# MM4_r0.net
KiCad netlist of a schematic drawn in EAGLE
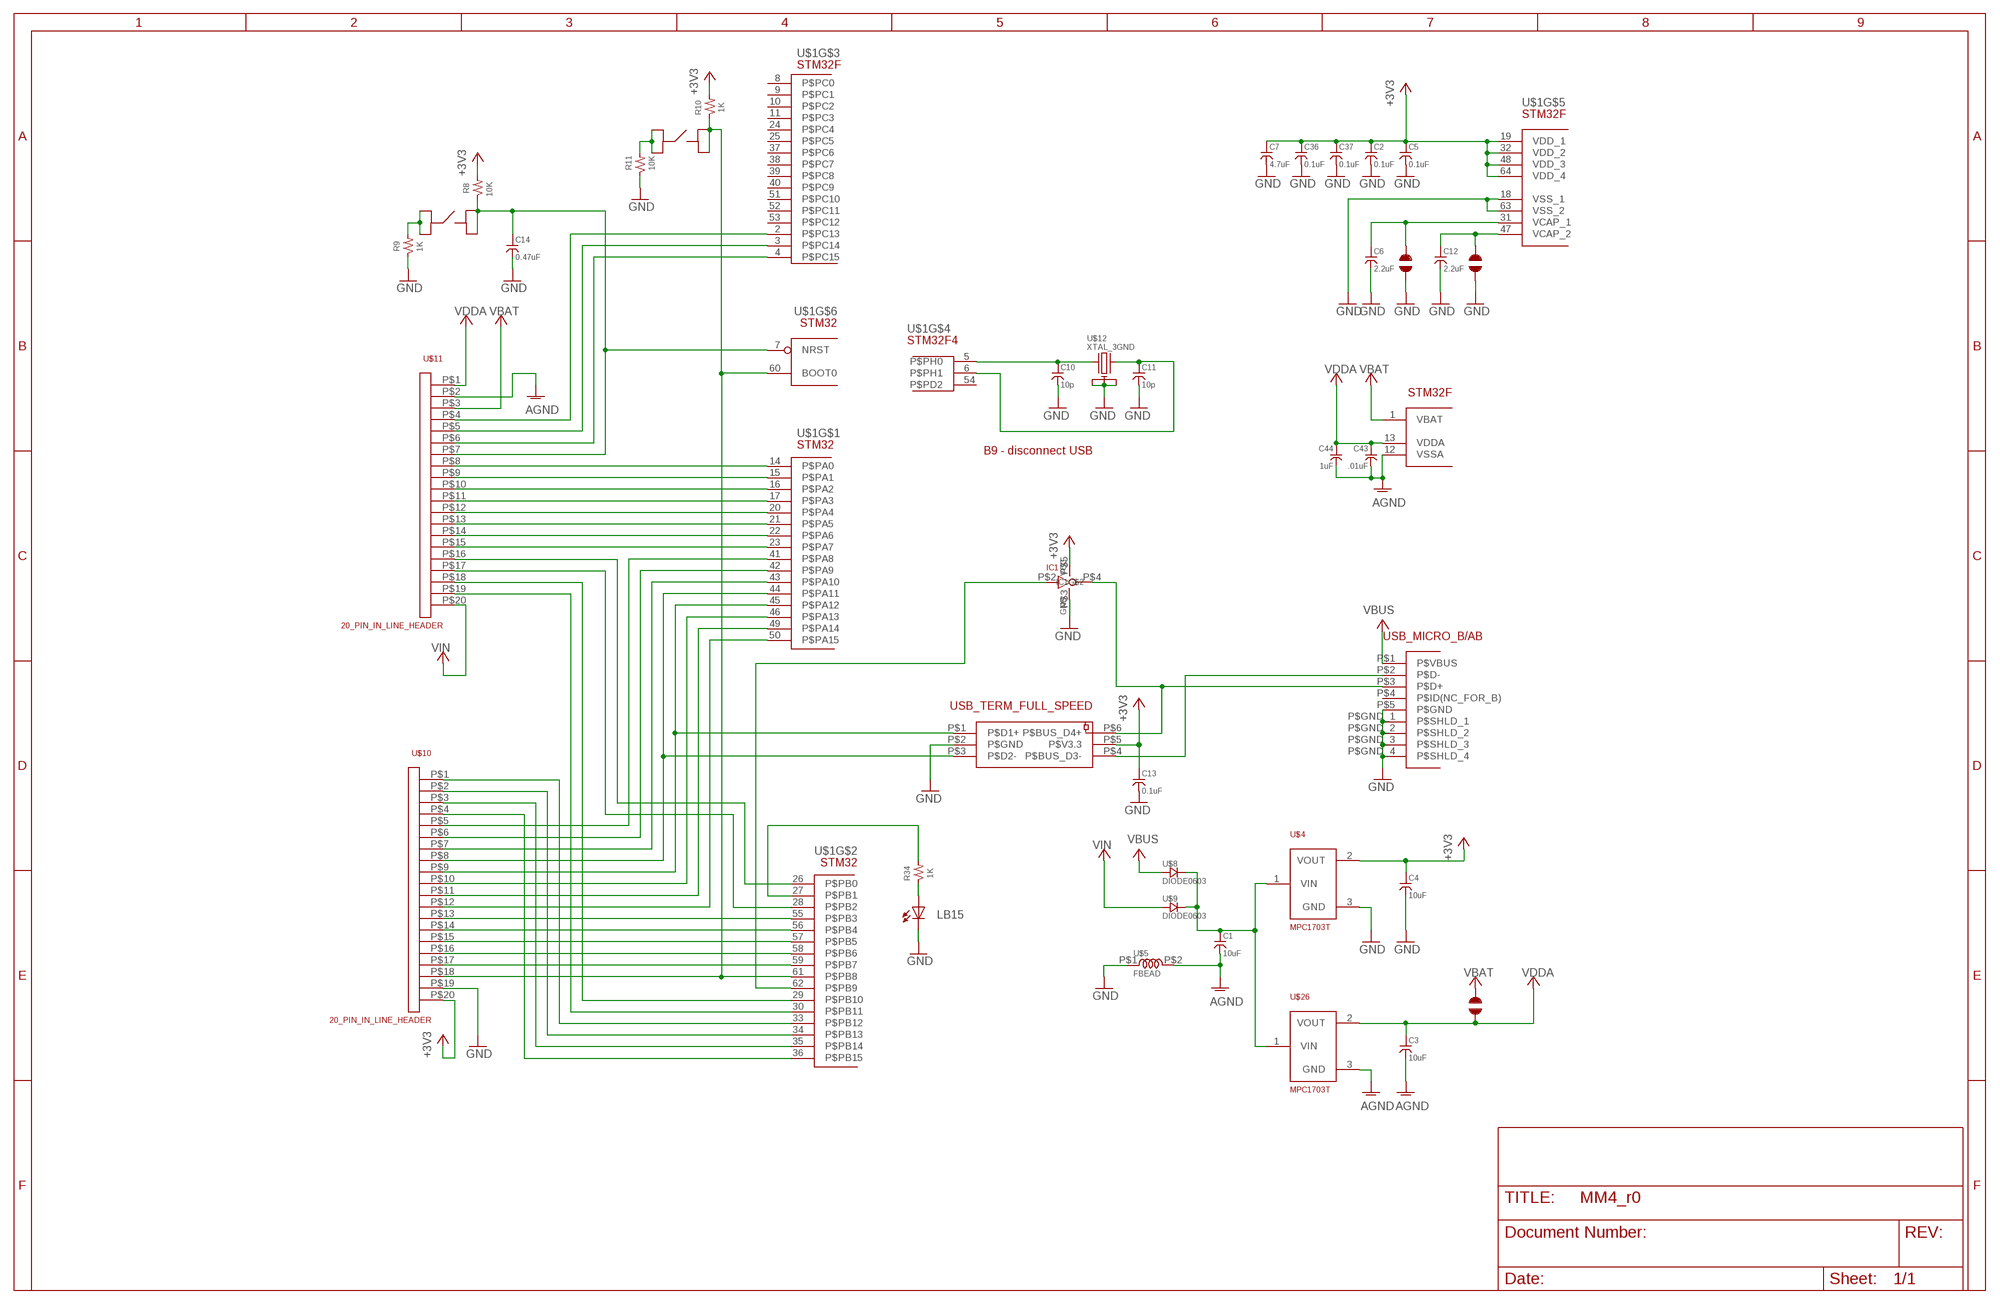
[diagram p0: schematic, sheet 1]

(export (version "E")
  (design (tool "Eeschema 10.0.6"))
  (components
    (comp (ref "C1")
      (value "10uF")
      (footprint "eagle-import:0603")
      (libsource (lib "eagle-import") (part "CAP0603"))
    )
    (comp (ref "C2")
      (value "0.1uF")
      (footprint "eagle-import:0603")
      (libsource (lib "eagle-import") (part "CAP0603"))
    )
    (comp (ref "C3")
      (value "10uF")
      (footprint "eagle-import:0603")
      (libsource (lib "eagle-import") (part "CAP0603"))
    )
    (comp (ref "C4")
      (value "10uF")
      (footprint "eagle-import:0603")
      (libsource (lib "eagle-import") (part "CAP0603"))
    )
    (comp (ref "C5")
      (value "0.1uF")
      (footprint "eagle-import:0603")
      (libsource (lib "eagle-import") (part "CAP0603"))
    )
    (comp (ref "C6")
      (value "2.2uF")
      (footprint "eagle-import:0603")
      (libsource (lib "eagle-import") (part "CAP0603"))
    )
    (comp (ref "C7")
      (value "4.7uF")
      (footprint "eagle-import:0603")
      (libsource (lib "eagle-import") (part "CAP0603"))
    )
    (comp (ref "C10")
      (value "10p")
      (footprint "eagle-import:0603")
      (libsource (lib "eagle-import") (part "CAP0603"))
    )
    (comp (ref "C11")
      (value "10p")
      (footprint "eagle-import:0603")
      (libsource (lib "eagle-import") (part "CAP0603"))
    )
    (comp (ref "C12")
      (value "2.2uF")
      (footprint "eagle-import:0603")
      (libsource (lib "eagle-import") (part "CAP0603"))
    )
    (comp (ref "C13")
      (value "0.1uF")
      (footprint "eagle-import:0603")
      (libsource (lib "eagle-import") (part "CAP0603"))
    )
    (comp (ref "C14")
      (value "0.47uF")
      (footprint "eagle-import:0603")
      (libsource (lib "eagle-import") (part "CAP0603"))
    )
    (comp (ref "C36")
      (value "0.1uF")
      (footprint "eagle-import:0603")
      (libsource (lib "eagle-import") (part "CAP0603"))
    )
    (comp (ref "C37")
      (value "0.1uF")
      (footprint "eagle-import:0603")
      (libsource (lib "eagle-import") (part "CAP0603"))
    )
    (comp (ref "C43")
      (value ".01uF")
      (footprint "eagle-import:0603")
      (libsource (lib "eagle-import") (part "CAP0603"))
    )
    (comp (ref "C44")
      (value "1uF")
      (footprint "eagle-import:0603")
      (libsource (lib "eagle-import") (part "CAP0603"))
    )
    (comp (ref "IC1")
      (value "7SZ05")
      (footprint "eagle-import:SC-70-5")
      (libsource (lib "eagle-import") (part "LOG_7SZ05"))
    )
    (comp (ref "LB15")
      (value "LED_CMD280603+")
      (footprint "eagle-import:0603+")
      (libsource (lib "eagle-import") (part "LED_CMD280603+"))
    )
    (comp (ref "R8")
      (value "10K")
      (footprint "eagle-import:0603")
      (libsource (lib "eagle-import") (part "RESISTOR0603"))
    )
    (comp (ref "R9")
      (value "1K")
      (footprint "eagle-import:0603")
      (libsource (lib "eagle-import") (part "RESISTOR0603"))
    )
    (comp (ref "R10")
      (value "1K")
      (footprint "eagle-import:0603")
      (libsource (lib "eagle-import") (part "RESISTOR0603"))
    )
    (comp (ref "R11")
      (value "10K")
      (footprint "eagle-import:0603")
      (libsource (lib "eagle-import") (part "RESISTOR0603"))
    )
    (comp (ref "R34")
      (value "1K")
      (footprint "eagle-import:0603")
      (libsource (lib "eagle-import") (part "RESISTOR0603"))
    )
    (comp (ref "U$1")
      (value "STM32F40XRG")
      (footprint "eagle-import:TQFP64")
      (libsource (lib "eagle-import") (part "STM32F40XRG"))
    )
    (comp (ref "U$2")
      (value "JUMPER_SOLDER")
      (footprint "eagle-import:JUMPER")
      (libsource (lib "eagle-import") (part "JUMPER_SOLDER"))
    )
    (comp (ref "U$3")
      (value "JUMPER_SOLDER")
      (footprint "eagle-import:JUMPER")
      (libsource (lib "eagle-import") (part "JUMPER_SOLDER"))
    )
    (comp (ref "U$4")
      (value "MPC1703T")
      (footprint "eagle-import:SOT23-3")
      (libsource (lib "eagle-import") (part "MPC1703T"))
    )
    (comp (ref "U$5")
      (value "FBEAD")
      (footprint "eagle-import:BEAD_0603")
      (libsource (lib "eagle-import") (part "FBEAD"))
    )
    (comp (ref "U$8")
      (value "DIODE0603")
      (footprint "eagle-import:0603_DIODE")
      (libsource (lib "eagle-import") (part "DIODE0603"))
    )
    (comp (ref "U$9")
      (value "DIODE0603")
      (footprint "eagle-import:0603_DIODE")
      (libsource (lib "eagle-import") (part "DIODE0603"))
    )
    (comp (ref "U$10")
      (value "20_PIN_IN_LINE_HEADER")
      (footprint "eagle-import:20_PIN_IN_LINE")
      (libsource (lib "eagle-import") (part "20_PIN_IN_LINE_HEADER"))
    )
    (comp (ref "U$11")
      (value "20_PIN_IN_LINE_HEADER")
      (footprint "eagle-import:20_PIN_IN_LINE")
      (libsource (lib "eagle-import") (part "20_PIN_IN_LINE_HEADER"))
    )
    (comp (ref "U$12")
      (value "XTAL_3GND")
      (footprint "eagle-import:XTAL=TXC7M-3")
      (libsource (lib "eagle-import") (part "XTAL_3GND"))
    )
    (comp (ref "U$13")
      (value "JUMPER_SOLDER")
      (footprint "eagle-import:JUMPER")
      (libsource (lib "eagle-import") (part "JUMPER_SOLDER"))
    )
    (comp (ref "U$14")
      (value "MICRO_USB_B")
      (footprint "eagle-import:USB-ZX-62-B-5PA")
      (libsource (lib "eagle-import") (part "MICRO_USB_BMICRO"))
    )
    (comp (ref "U$23")
      (value "USB_TERM_FS")
      (footprint "eagle-import:SOT-666IP")
      (libsource (lib "eagle-import") (part "USB_TERM_FS"))
    )
    (comp (ref "U$24")
      (value "SW_SMD_TACTILE")
      (footprint "eagle-import:SW_SMD_TACTILE")
      (libsource (lib "eagle-import") (part "SW_SMD_TACTILE"))
    )
    (comp (ref "U$25")
      (value "SW_SMD_TACTILE")
      (footprint "eagle-import:SW_SMD_TACTILE")
      (libsource (lib "eagle-import") (part "SW_SMD_TACTILE"))
    )
    (comp (ref "U$26")
      (value "MPC1703T")
      (footprint "eagle-import:SOT23-3")
      (libsource (lib "eagle-import") (part "MPC1703T"))
    )
  )
  (nets
    (net (code "1") (name "+3V3") (class "Default")
      (node (ref "C13") (pin "P$1") (pinfunction "P$1_P$1") (pintype "passive"))
      (node (ref "C2") (pin "P$1") (pinfunction "P$1_P$1") (pintype "passive"))
      (node (ref "C36") (pin "P$1") (pinfunction "P$1_P$1") (pintype "passive"))
      (node (ref "C37") (pin "P$1") (pinfunction "P$1_P$1") (pintype "passive"))
      (node (ref "C4") (pin "P$1") (pinfunction "P$1_P$1") (pintype "passive"))
      (node (ref "C5") (pin "P$1") (pinfunction "P$1_P$1") (pintype "passive"))
      (node (ref "C7") (pin "P$1") (pinfunction "P$1_P$1") (pintype "passive"))
      (node (ref "IC1") (pin "P$5") (pinfunction "VCC_P$5") (pintype "power_in"))
      (node (ref "R10") (pin "P$1") (pinfunction "P$2_P$1") (pintype "passive"))
      (node (ref "R8") (pin "P$1") (pinfunction "P$2_P$1") (pintype "passive"))
      (node (ref "U$1") (pin "19") (pinfunction "VDD_1_19") (pintype "power_in"))
      (node (ref "U$1") (pin "32") (pinfunction "VDD_2_32") (pintype "power_in"))
      (node (ref "U$1") (pin "48") (pinfunction "VDD_3_48") (pintype "power_in"))
      (node (ref "U$1") (pin "64") (pinfunction "VDD_4_64") (pintype "power_in"))
      (node (ref "U$10") (pin "P$20") (pinfunction "P$20_P$20") (pintype "bidirectional"))
      (node (ref "U$23") (pin "P$5") (pinfunction "P$V3.3_P$5") (pintype "bidirectional"))
      (node (ref "U$4") (pin "2") (pinfunction "VOUT_2") (pintype "power_in"))
    )
    (net (code "2") (name "AGND") (class "Default")
      (node (ref "C1") (pin "P$2") (pinfunction "P$2_P$2") (pintype "passive"))
      (node (ref "C3") (pin "P$2") (pinfunction "P$2_P$2") (pintype "passive"))
      (node (ref "C43") (pin "P$2") (pinfunction "P$2_P$2") (pintype "passive"))
      (node (ref "C44") (pin "P$2") (pinfunction "P$2_P$2") (pintype "passive"))
      (node (ref "U$1") (pin "12") (pinfunction "VSSA_12") (pintype "power_in"))
      (node (ref "U$11") (pin "P$2") (pinfunction "P$2_P$2") (pintype "bidirectional"))
      (node (ref "U$26") (pin "3") (pinfunction "GND_3") (pintype "power_in"))
      (node (ref "U$5") (pin "P$2") (pinfunction "P$2_P$2") (pintype "bidirectional"))
    )
    (net (code "3") (name "GND") (class "Default")
      (node (ref "C10") (pin "P$2") (pinfunction "P$2_P$2") (pintype "passive"))
      (node (ref "C11") (pin "P$2") (pinfunction "P$2_P$2") (pintype "passive"))
      (node (ref "C12") (pin "P$2") (pinfunction "P$2_P$2") (pintype "passive"))
      (node (ref "C13") (pin "P$2") (pinfunction "P$2_P$2") (pintype "passive"))
      (node (ref "C14") (pin "P$2") (pinfunction "P$2_P$2") (pintype "passive"))
      (node (ref "C2") (pin "P$2") (pinfunction "P$2_P$2") (pintype "passive"))
      (node (ref "C36") (pin "P$2") (pinfunction "P$2_P$2") (pintype "passive"))
      (node (ref "C37") (pin "P$2") (pinfunction "P$2_P$2") (pintype "passive"))
      (node (ref "C4") (pin "P$2") (pinfunction "P$2_P$2") (pintype "passive"))
      (node (ref "C5") (pin "P$2") (pinfunction "P$2_P$2") (pintype "passive"))
      (node (ref "C6") (pin "P$2") (pinfunction "P$2_P$2") (pintype "passive"))
      (node (ref "C7") (pin "P$2") (pinfunction "P$2_P$2") (pintype "passive"))
      (node (ref "IC1") (pin "P$3") (pinfunction "GND_P$3") (pintype "power_in"))
      (node (ref "LB15") (pin "P$2-") (pinfunction "C_P$2-") (pintype "passive"))
      (node (ref "R11") (pin "P$2") (pinfunction "P$1_P$2") (pintype "passive"))
      (node (ref "R9") (pin "P$2") (pinfunction "P$1_P$2") (pintype "passive"))
      (node (ref "U$1") (pin "18") (pinfunction "VSS_1_18") (pintype "power_in"))
      (node (ref "U$1") (pin "63") (pinfunction "VSS_2_63") (pintype "power_in"))
      (node (ref "U$10") (pin "P$19") (pinfunction "P$19_P$19") (pintype "bidirectional"))
      (node (ref "U$12") (pin "GND") (pinfunction "P$GND_1_GND") (pintype "power_in"))
      (node (ref "U$12") (pin "P$2") (pinfunction "P$GND_2_P$2") (pintype "power_in"))
      (node (ref "U$12") (pin "P$4") (pinfunction "P$GND_3_P$4") (pintype "power_in"))
      (node (ref "U$14") (pin "P$5") (pinfunction "P$GND_P$5") (pintype "power_in"))
      (node (ref "U$14") (pin "P$GND_1") (pinfunction "P$SHLD_1_P$GND_1") (pintype "bidirectional"))
      (node (ref "U$14") (pin "P$GND_2") (pinfunction "P$SHLD_2_P$GND_2") (pintype "bidirectional"))
      (node (ref "U$14") (pin "P$GND_3") (pinfunction "P$SHLD_3_P$GND_3") (pintype "bidirectional"))
      (node (ref "U$14") (pin "P$GND_4") (pinfunction "P$SHLD_4_P$GND_4") (pintype "bidirectional"))
      (node (ref "U$2") (pin "P$1") (pinfunction "P$1_P$1") (pintype "bidirectional"))
      (node (ref "U$23") (pin "P$2") (pinfunction "P$GND_P$2") (pintype "power_in"))
      (node (ref "U$3") (pin "P$1") (pinfunction "P$1_P$1") (pintype "bidirectional"))
      (node (ref "U$4") (pin "3") (pinfunction "GND_3") (pintype "power_in"))
      (node (ref "U$5") (pin "P$1") (pinfunction "P$1_P$1") (pintype "bidirectional"))
    )
    (net (code "4") (name "Net-(IC1A-P$IN)") (class "Default")
      (node (ref "IC1") (pin "P$2") (pinfunction "P$IN_P$2") (pintype "input"))
      (node (ref "U$1") (pin "62") (pinfunction "P$PB9_62") (pintype "bidirectional"))
    )
    (net (code "5") (name "Net-(IC1A-P$OUT)") (class "Default")
      (node (ref "IC1") (pin "P$4") (pinfunction "P$OUT_P$4") (pintype "output"))
      (node (ref "U$14") (pin "P$3") (pinfunction "P$D+_P$3") (pintype "bidirectional"))
      (node (ref "U$23") (pin "P$6") (pinfunction "P$BUS_D4+_P$6") (pintype "bidirectional"))
    )
    (net (code "6") (name "Net-(LB15-A)") (class "Default")
      (node (ref "LB15") (pin "P$1+") (pinfunction "A_P$1+") (pintype "passive"))
      (node (ref "R34") (pin "P$2") (pinfunction "P$1_P$2") (pintype "passive"))
    )
    (net (code "7") (name "Net-(R8-P$1)") (class "Default")
      (node (ref "C14") (pin "P$1") (pinfunction "P$1_P$1") (pintype "passive"))
      (node (ref "R8") (pin "P$2") (pinfunction "P$1_P$2") (pintype "passive"))
      (node (ref "U$1") (pin "7") (pinfunction "NRST_7") (pintype "input"))
      (node (ref "U$11") (pin "P$7") (pinfunction "P$7_P$7") (pintype "bidirectional"))
      (node (ref "U$25") (pin "P$3") (pinfunction "P$3_P$3") (pintype "bidirectional"))
      (node (ref "U$25") (pin "P$4") (pinfunction "P$4_P$4") (pintype "bidirectional"))
    )
    (net (code "8") (name "Net-(R9-P$2)") (class "Default")
      (node (ref "R9") (pin "P$1") (pinfunction "P$2_P$1") (pintype "passive"))
      (node (ref "U$25") (pin "P$1") (pinfunction "P$1_P$1") (pintype "bidirectional"))
      (node (ref "U$25") (pin "P$2") (pinfunction "P$2_P$2") (pintype "bidirectional"))
    )
    (net (code "9") (name "Net-(R10-P$1)") (class "Default")
      (node (ref "R10") (pin "P$2") (pinfunction "P$1_P$2") (pintype "passive"))
      (node (ref "U$1") (pin "60") (pinfunction "BOOT0_60") (pintype "input"))
      (node (ref "U$1") (pin "61") (pinfunction "P$PB8_61") (pintype "bidirectional"))
      (node (ref "U$10") (pin "P$18") (pinfunction "P$18_P$18") (pintype "bidirectional"))
      (node (ref "U$24") (pin "P$3") (pinfunction "P$3_P$3") (pintype "bidirectional"))
      (node (ref "U$24") (pin "P$4") (pinfunction "P$4_P$4") (pintype "bidirectional"))
    )
    (net (code "10") (name "Net-(R11-P$2)") (class "Default")
      (node (ref "R11") (pin "P$1") (pinfunction "P$2_P$1") (pintype "passive"))
      (node (ref "U$24") (pin "P$1") (pinfunction "P$1_P$1") (pintype "bidirectional"))
      (node (ref "U$24") (pin "P$2") (pinfunction "P$2_P$2") (pintype "bidirectional"))
    )
    (net (code "11") (name "Net-(R34-P$2)") (class "Default")
      (node (ref "R34") (pin "P$1") (pinfunction "P$2_P$1") (pintype "passive"))
      (node (ref "U$1") (pin "27") (pinfunction "P$PB1_27") (pintype "bidirectional"))
    )
    (net (code "12") (name "Net-(U$1A-P$PA0)") (class "Default")
      (node (ref "U$1") (pin "14") (pinfunction "P$PA0_14") (pintype "bidirectional"))
      (node (ref "U$11") (pin "P$8") (pinfunction "P$8_P$8") (pintype "bidirectional"))
    )
    (net (code "13") (name "Net-(U$1A-P$PA1)") (class "Default")
      (node (ref "U$1") (pin "15") (pinfunction "P$PA1_15") (pintype "bidirectional"))
      (node (ref "U$11") (pin "P$9") (pinfunction "P$9_P$9") (pintype "bidirectional"))
    )
    (net (code "14") (name "Net-(U$1A-P$PA2)") (class "Default")
      (node (ref "U$1") (pin "16") (pinfunction "P$PA2_16") (pintype "bidirectional"))
      (node (ref "U$11") (pin "P$10") (pinfunction "P$10_P$10") (pintype "bidirectional"))
    )
    (net (code "15") (name "Net-(U$1A-P$PA3)") (class "Default")
      (node (ref "U$1") (pin "17") (pinfunction "P$PA3_17") (pintype "bidirectional"))
      (node (ref "U$11") (pin "P$11") (pinfunction "P$11_P$11") (pintype "bidirectional"))
    )
    (net (code "16") (name "Net-(U$1A-P$PA4)") (class "Default")
      (node (ref "U$1") (pin "20") (pinfunction "P$PA4_20") (pintype "bidirectional"))
      (node (ref "U$11") (pin "P$12") (pinfunction "P$12_P$12") (pintype "bidirectional"))
    )
    (net (code "17") (name "Net-(U$1A-P$PA5)") (class "Default")
      (node (ref "U$1") (pin "21") (pinfunction "P$PA5_21") (pintype "bidirectional"))
      (node (ref "U$11") (pin "P$13") (pinfunction "P$13_P$13") (pintype "bidirectional"))
    )
    (net (code "18") (name "Net-(U$1A-P$PA6)") (class "Default")
      (node (ref "U$1") (pin "22") (pinfunction "P$PA6_22") (pintype "bidirectional"))
      (node (ref "U$11") (pin "P$14") (pinfunction "P$14_P$14") (pintype "bidirectional"))
    )
    (net (code "19") (name "Net-(U$1A-P$PA7)") (class "Default")
      (node (ref "U$1") (pin "23") (pinfunction "P$PA7_23") (pintype "bidirectional"))
      (node (ref "U$11") (pin "P$15") (pinfunction "P$15_P$15") (pintype "bidirectional"))
    )
    (net (code "20") (name "Net-(U$1A-P$PA8)") (class "Default")
      (node (ref "U$1") (pin "41") (pinfunction "P$PA8_41") (pintype "bidirectional"))
      (node (ref "U$10") (pin "P$5") (pinfunction "P$5_P$5") (pintype "bidirectional"))
    )
    (net (code "21") (name "Net-(U$1A-P$PA9)") (class "Default")
      (node (ref "U$1") (pin "42") (pinfunction "P$PA9_42") (pintype "bidirectional"))
      (node (ref "U$10") (pin "P$6") (pinfunction "P$6_P$6") (pintype "bidirectional"))
    )
    (net (code "22") (name "Net-(U$1A-P$PA10)") (class "Default")
      (node (ref "U$1") (pin "43") (pinfunction "P$PA10_43") (pintype "bidirectional"))
      (node (ref "U$10") (pin "P$7") (pinfunction "P$7_P$7") (pintype "bidirectional"))
    )
    (net (code "23") (name "Net-(U$1A-P$PA11)") (class "Default")
      (node (ref "U$1") (pin "44") (pinfunction "P$PA11_44") (pintype "bidirectional"))
      (node (ref "U$10") (pin "P$8") (pinfunction "P$8_P$8") (pintype "bidirectional"))
      (node (ref "U$23") (pin "P$3") (pinfunction "P$D2-_P$3") (pintype "bidirectional"))
    )
    (net (code "24") (name "Net-(U$1A-P$PA12)") (class "Default")
      (node (ref "U$1") (pin "45") (pinfunction "P$PA12_45") (pintype "bidirectional"))
      (node (ref "U$10") (pin "P$9") (pinfunction "P$9_P$9") (pintype "bidirectional"))
      (node (ref "U$23") (pin "P$1") (pinfunction "P$D1+_P$1") (pintype "bidirectional"))
    )
    (net (code "25") (name "Net-(U$1A-P$PA13)") (class "Default")
      (node (ref "U$1") (pin "46") (pinfunction "P$PA13_46") (pintype "bidirectional"))
      (node (ref "U$10") (pin "P$10") (pinfunction "P$10_P$10") (pintype "bidirectional"))
    )
    (net (code "26") (name "Net-(U$1A-P$PA14)") (class "Default")
      (node (ref "U$1") (pin "49") (pinfunction "P$PA14_49") (pintype "bidirectional"))
      (node (ref "U$10") (pin "P$11") (pinfunction "P$11_P$11") (pintype "bidirectional"))
    )
    (net (code "27") (name "Net-(U$1A-P$PA15)") (class "Default")
      (node (ref "U$1") (pin "50") (pinfunction "P$PA15_50") (pintype "bidirectional"))
      (node (ref "U$10") (pin "P$12") (pinfunction "P$12_P$12") (pintype "bidirectional"))
    )
    (net (code "28") (name "Net-(U$1B-P$PB0)") (class "Default")
      (node (ref "U$1") (pin "26") (pinfunction "P$PB0_26") (pintype "bidirectional"))
      (node (ref "U$11") (pin "P$16") (pinfunction "P$16_P$16") (pintype "bidirectional"))
    )
    (net (code "29") (name "Net-(U$1B-P$PB2)") (class "Default")
      (node (ref "U$1") (pin "28") (pinfunction "P$PB2_28") (pintype "bidirectional"))
      (node (ref "U$11") (pin "P$17") (pinfunction "P$17_P$17") (pintype "bidirectional"))
    )
    (net (code "30") (name "Net-(U$1B-P$PB3)") (class "Default")
      (node (ref "U$1") (pin "55") (pinfunction "P$PB3_55") (pintype "bidirectional"))
      (node (ref "U$10") (pin "P$13") (pinfunction "P$13_P$13") (pintype "bidirectional"))
    )
    (net (code "31") (name "Net-(U$1B-P$PB4)") (class "Default")
      (node (ref "U$1") (pin "56") (pinfunction "P$PB4_56") (pintype "bidirectional"))
      (node (ref "U$10") (pin "P$14") (pinfunction "P$14_P$14") (pintype "bidirectional"))
    )
    (net (code "32") (name "Net-(U$1B-P$PB5)") (class "Default")
      (node (ref "U$1") (pin "57") (pinfunction "P$PB5_57") (pintype "bidirectional"))
      (node (ref "U$10") (pin "P$15") (pinfunction "P$15_P$15") (pintype "bidirectional"))
    )
    (net (code "33") (name "Net-(U$1B-P$PB6)") (class "Default")
      (node (ref "U$1") (pin "58") (pinfunction "P$PB6_58") (pintype "bidirectional"))
      (node (ref "U$10") (pin "P$16") (pinfunction "P$16_P$16") (pintype "bidirectional"))
    )
    (net (code "34") (name "Net-(U$1B-P$PB7)") (class "Default")
      (node (ref "U$1") (pin "59") (pinfunction "P$PB7_59") (pintype "bidirectional"))
      (node (ref "U$10") (pin "P$17") (pinfunction "P$17_P$17") (pintype "bidirectional"))
    )
    (net (code "35") (name "Net-(U$1B-P$PB10)") (class "Default")
      (node (ref "U$1") (pin "29") (pinfunction "P$PB10_29") (pintype "bidirectional"))
      (node (ref "U$11") (pin "P$18") (pinfunction "P$18_P$18") (pintype "bidirectional"))
    )
    (net (code "36") (name "Net-(U$1B-P$PB11)") (class "Default")
      (node (ref "U$1") (pin "30") (pinfunction "P$PB11_30") (pintype "bidirectional"))
      (node (ref "U$11") (pin "P$19") (pinfunction "P$19_P$19") (pintype "bidirectional"))
    )
    (net (code "37") (name "Net-(U$1B-P$PB12)") (class "Default")
      (node (ref "U$1") (pin "33") (pinfunction "P$PB12_33") (pintype "bidirectional"))
      (node (ref "U$10") (pin "P$1") (pinfunction "P$1_P$1") (pintype "bidirectional"))
    )
    (net (code "38") (name "Net-(U$1B-P$PB13)") (class "Default")
      (node (ref "U$1") (pin "34") (pinfunction "P$PB13_34") (pintype "bidirectional"))
      (node (ref "U$10") (pin "P$2") (pinfunction "P$2_P$2") (pintype "bidirectional"))
    )
    (net (code "39") (name "Net-(U$1B-P$PB14)") (class "Default")
      (node (ref "U$1") (pin "35") (pinfunction "P$PB14_35") (pintype "bidirectional"))
      (node (ref "U$10") (pin "P$3") (pinfunction "P$3_P$3") (pintype "bidirectional"))
    )
    (net (code "40") (name "Net-(U$1B-P$PB15)") (class "Default")
      (node (ref "U$1") (pin "36") (pinfunction "P$PB15_36") (pintype "bidirectional"))
      (node (ref "U$10") (pin "P$4") (pinfunction "P$4_P$4") (pintype "bidirectional"))
    )
    (net (code "41") (name "Net-(U$1C-P$PC13)") (class "Default")
      (node (ref "U$1") (pin "2") (pinfunction "P$PC13_2") (pintype "bidirectional"))
      (node (ref "U$11") (pin "P$4") (pinfunction "P$4_P$4") (pintype "bidirectional"))
    )
    (net (code "42") (name "Net-(U$1C-P$PC14)") (class "Default")
      (node (ref "U$1") (pin "3") (pinfunction "P$PC14_3") (pintype "bidirectional"))
      (node (ref "U$11") (pin "P$5") (pinfunction "P$5_P$5") (pintype "bidirectional"))
    )
    (net (code "43") (name "Net-(U$1C-P$PC15)") (class "Default")
      (node (ref "U$1") (pin "4") (pinfunction "P$PC15_4") (pintype "bidirectional"))
      (node (ref "U$11") (pin "P$6") (pinfunction "P$6_P$6") (pintype "bidirectional"))
    )
    (net (code "44") (name "Net-(U$1E-VCAP_1)") (class "Default")
      (node (ref "C6") (pin "P$1") (pinfunction "P$1_P$1") (pintype "passive"))
      (node (ref "U$1") (pin "31") (pinfunction "VCAP_1_31") (pintype "power_in"))
      (node (ref "U$2") (pin "P$2") (pinfunction "P$2_P$2") (pintype "bidirectional"))
    )
    (net (code "45") (name "Net-(U$1E-VCAP_2)") (class "Default")
      (node (ref "C12") (pin "P$1") (pinfunction "P$1_P$1") (pintype "passive"))
      (node (ref "U$1") (pin "47") (pinfunction "VCAP_2_47") (pintype "power_in"))
      (node (ref "U$3") (pin "P$2") (pinfunction "P$2_P$2") (pintype "bidirectional"))
    )
    (net (code "46") (name "Net-(U$12-P$XT1)") (class "Default")
      (node (ref "C10") (pin "P$1") (pinfunction "P$1_P$1") (pintype "passive"))
      (node (ref "U$1") (pin "5") (pinfunction "P$PH0_5") (pintype "bidirectional"))
      (node (ref "U$12") (pin "P$1") (pinfunction "P$XT1_P$1") (pintype "bidirectional"))
    )
    (net (code "47") (name "Net-(U$12-P$XT2)") (class "Default")
      (node (ref "C11") (pin "P$1") (pinfunction "P$1_P$1") (pintype "passive"))
      (node (ref "U$1") (pin "6") (pinfunction "P$PH1_6") (pintype "bidirectional"))
      (node (ref "U$12") (pin "P$3") (pinfunction "P$XT2_P$3") (pintype "bidirectional"))
    )
    (net (code "48") (name "Net-(U$14-P$D-)") (class "Default")
      (node (ref "U$14") (pin "P$2") (pinfunction "P$D-_P$2") (pintype "bidirectional"))
      (node (ref "U$23") (pin "P$4") (pinfunction "P$BUS_D3-_P$4") (pintype "bidirectional"))
    )
    (net (code "49") (name "Net-(U$26-VIN)") (class "Default")
      (node (ref "C1") (pin "P$1") (pinfunction "P$1_P$1") (pintype "passive"))
      (node (ref "U$26") (pin "1") (pinfunction "VIN_1") (pintype "power_in"))
      (node (ref "U$4") (pin "1") (pinfunction "VIN_1") (pintype "power_in"))
      (node (ref "U$8") (pin "P$2") (pinfunction "P$2_P$2") (pintype "bidirectional"))
      (node (ref "U$9") (pin "P$2") (pinfunction "P$2_P$2") (pintype "bidirectional"))
    )
    (net (code "50") (name "VBAT") (class "Default")
      (node (ref "U$1") (pin "1") (pinfunction "VBAT_1") (pintype "power_in"))
      (node (ref "U$11") (pin "P$3") (pinfunction "P$3_P$3") (pintype "bidirectional"))
      (node (ref "U$13") (pin "P$2") (pinfunction "P$2_P$2") (pintype "bidirectional"))
    )
    (net (code "51") (name "VBUS") (class "Default")
      (node (ref "U$14") (pin "P$1") (pinfunction "P$VBUS_P$1") (pintype "power_in"))
      (node (ref "U$8") (pin "P$1") (pinfunction "P$1_P$1") (pintype "bidirectional"))
    )
    (net (code "52") (name "VDDA") (class "Default")
      (node (ref "C3") (pin "P$1") (pinfunction "P$1_P$1") (pintype "passive"))
      (node (ref "C43") (pin "P$1") (pinfunction "P$1_P$1") (pintype "passive"))
      (node (ref "C44") (pin "P$1") (pinfunction "P$1_P$1") (pintype "passive"))
      (node (ref "U$1") (pin "13") (pinfunction "VDDA_13") (pintype "power_in"))
      (node (ref "U$11") (pin "P$1") (pinfunction "P$1_P$1") (pintype "bidirectional"))
      (node (ref "U$13") (pin "P$1") (pinfunction "P$1_P$1") (pintype "bidirectional"))
      (node (ref "U$26") (pin "2") (pinfunction "VOUT_2") (pintype "power_in"))
    )
    (net (code "53") (name "VIN") (class "Default")
      (node (ref "U$11") (pin "P$20") (pinfunction "P$20_P$20") (pintype "bidirectional"))
      (node (ref "U$9") (pin "P$1") (pinfunction "P$1_P$1") (pintype "bidirectional"))
    )
    (net (code "54") (name "unconnected-(U$1C-P$PC0-Pad8)") (class "Default")
      (node (ref "U$1") (pin "8") (pinfunction "P$PC0_8") (pintype "bidirectional"))
    )
    (net (code "55") (name "unconnected-(U$1C-P$PC1-Pad9)") (class "Default")
      (node (ref "U$1") (pin "9") (pinfunction "P$PC1_9") (pintype "bidirectional"))
    )
    (net (code "56") (name "unconnected-(U$1C-P$PC2-Pad10)") (class "Default")
      (node (ref "U$1") (pin "10") (pinfunction "P$PC2_10") (pintype "bidirectional"))
    )
    (net (code "57") (name "unconnected-(U$1C-P$PC3-Pad11)") (class "Default")
      (node (ref "U$1") (pin "11") (pinfunction "P$PC3_11") (pintype "bidirectional"))
    )
    (net (code "58") (name "unconnected-(U$1C-P$PC4-Pad24)") (class "Default")
      (node (ref "U$1") (pin "24") (pinfunction "P$PC4_24") (pintype "bidirectional"))
    )
    (net (code "59") (name "unconnected-(U$1C-P$PC5-Pad25)") (class "Default")
      (node (ref "U$1") (pin "25") (pinfunction "P$PC5_25") (pintype "bidirectional"))
    )
    (net (code "60") (name "unconnected-(U$1C-P$PC6-Pad37)") (class "Default")
      (node (ref "U$1") (pin "37") (pinfunction "P$PC6_37") (pintype "bidirectional"))
    )
    (net (code "61") (name "unconnected-(U$1C-P$PC7-Pad38)") (class "Default")
      (node (ref "U$1") (pin "38") (pinfunction "P$PC7_38") (pintype "bidirectional"))
    )
    (net (code "62") (name "unconnected-(U$1C-P$PC8-Pad39)") (class "Default")
      (node (ref "U$1") (pin "39") (pinfunction "P$PC8_39") (pintype "bidirectional"))
    )
    (net (code "63") (name "unconnected-(U$1C-P$PC9-Pad40)") (class "Default")
      (node (ref "U$1") (pin "40") (pinfunction "P$PC9_40") (pintype "bidirectional"))
    )
    (net (code "64") (name "unconnected-(U$1C-P$PC10-Pad51)") (class "Default")
      (node (ref "U$1") (pin "51") (pinfunction "P$PC10_51") (pintype "bidirectional"))
    )
    (net (code "65") (name "unconnected-(U$1C-P$PC11-Pad52)") (class "Default")
      (node (ref "U$1") (pin "52") (pinfunction "P$PC11_52") (pintype "bidirectional"))
    )
    (net (code "66") (name "unconnected-(U$1C-P$PC12-Pad53)") (class "Default")
      (node (ref "U$1") (pin "53") (pinfunction "P$PC12_53") (pintype "bidirectional"))
    )
    (net (code "67") (name "unconnected-(U$1D-P$PD2-Pad54)") (class "Default")
      (node (ref "U$1") (pin "54") (pinfunction "P$PD2_54") (pintype "bidirectional"))
    )
    (net (code "68") (name "unconnected-(U$14-P$ID(NC_FOR_B)-PadP$4)") (class "Default")
      (node (ref "U$14") (pin "P$4") (pinfunction "P$ID(NC_FOR_B)_P$4") (pintype "no_connect"))
    )
  )
)
